# Schematic.net
KiCad netlist of a schematic drawn in Altium Designer
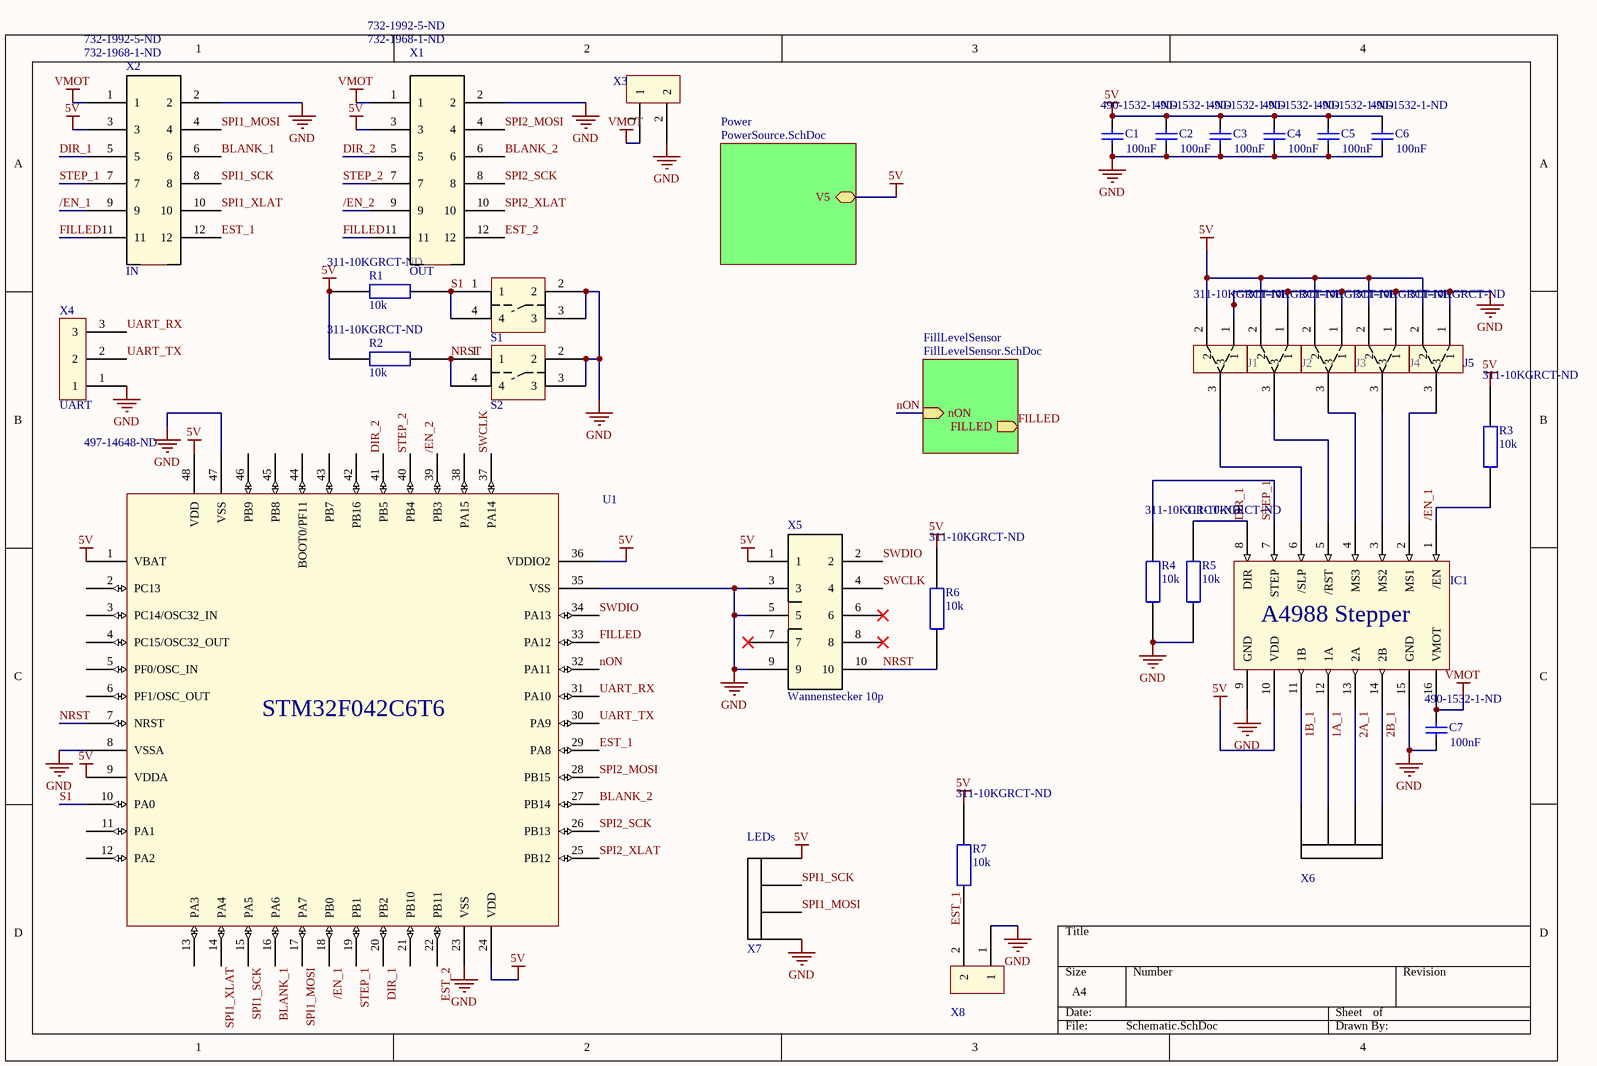
[diagram p0: Schematic.SchDoc]

(export (version "E")
  (design (tool "Eeschema 10.0.6"))
  (components
    (comp (ref "C1")
      (value "100nF")
      (footprint "Res 0603")
      (description "Capacitor")
      (fields
        (field (name "SUPPLIER PART NUMBER 1") "490-1532-1-ND")
        (field (name "Comment") "Cap")
        (field (name "PUBLISHER") "Altium Limited")
      )
      (libsource (lib "Miscellaneous Devices") (part "Cap"))
    )
    (comp (ref "C2")
      (value "100nF")
      (footprint "Res 0603")
      (description "Capacitor")
      (fields
        (field (name "SUPPLIER PART NUMBER 1") "490-1532-1-ND")
        (field (name "Comment") "Cap")
        (field (name "PUBLISHER") "Altium Limited")
      )
      (libsource (lib "Miscellaneous Devices") (part "Cap"))
    )
    (comp (ref "C3")
      (value "100nF")
      (footprint "Res 0603")
      (description "Capacitor")
      (fields
        (field (name "SUPPLIER PART NUMBER 1") "490-1532-1-ND")
        (field (name "Comment") "Cap")
        (field (name "PUBLISHER") "Altium Limited")
      )
      (libsource (lib "Miscellaneous Devices") (part "Cap"))
    )
    (comp (ref "C4")
      (value "100nF")
      (footprint "Res 0603")
      (description "Capacitor")
      (fields
        (field (name "SUPPLIER PART NUMBER 1") "490-1532-1-ND")
        (field (name "Comment") "Cap")
        (field (name "PUBLISHER") "Altium Limited")
      )
      (libsource (lib "Miscellaneous Devices") (part "Cap"))
    )
    (comp (ref "C5")
      (value "100nF")
      (footprint "Res 0603")
      (description "Capacitor")
      (fields
        (field (name "SUPPLIER PART NUMBER 1") "490-1532-1-ND")
        (field (name "Comment") "Cap")
        (field (name "PUBLISHER") "Altium Limited")
      )
      (libsource (lib "Miscellaneous Devices") (part "Cap"))
    )
    (comp (ref "C6")
      (value "100nF")
      (footprint "Res 0603")
      (description "Capacitor")
      (fields
        (field (name "SUPPLIER PART NUMBER 1") "490-1532-1-ND")
        (field (name "Comment") "Cap")
        (field (name "PUBLISHER") "Altium Limited")
      )
      (libsource (lib "Miscellaneous Devices") (part "Cap"))
    )
    (comp (ref "C7")
      (value "100nF")
      (footprint "Res 0603")
      (description "Capacitor")
      (fields
        (field (name "SUPPLIER PART NUMBER 1") "490-1532-1-ND")
        (field (name "Comment") "Cap")
        (field (name "PUBLISHER") "Altium Limited")
      )
      (libsource (lib "Miscellaneous Devices") (part "Cap"))
    )
    (comp (ref "IC1")
      (value "A4988 Stepper")
      (footprint "A4988 Stepper")
      (libsource (lib "Schlib") (part "A4988 Stepper"))
    )
    (comp (ref "J1")
      (value "VCC to GND Jumper")
      (footprint "VCC to GND Jumper")
      (fields (field (name "SUPPLIER PART NUMBER 1") "311-10KGRCT-ND"))
      (libsource (lib "Schlib") (part "VCC to GND Jumper"))
    )
    (comp (ref "J2")
      (value "VCC to GND Jumper")
      (footprint "VCC to GND Jumper")
      (fields (field (name "SUPPLIER PART NUMBER 1") "311-10KGRCT-ND"))
      (libsource (lib "Schlib") (part "VCC to GND Jumper"))
    )
    (comp (ref "J3")
      (value "VCC to GND Jumper")
      (footprint "VCC to GND Jumper")
      (fields (field (name "SUPPLIER PART NUMBER 1") "311-10KGRCT-ND"))
      (libsource (lib "Schlib") (part "VCC to GND Jumper"))
    )
    (comp (ref "J4")
      (value "VCC to GND Jumper")
      (footprint "VCC to GND Jumper")
      (fields (field (name "SUPPLIER PART NUMBER 1") "311-10KGRCT-ND"))
      (libsource (lib "Schlib") (part "VCC to GND Jumper"))
    )
    (comp (ref "J5")
      (value "VCC to GND Jumper")
      (footprint "VCC to GND Jumper")
      (fields (field (name "SUPPLIER PART NUMBER 1") "311-10KGRCT-ND"))
      (libsource (lib "Schlib") (part "VCC to GND Jumper"))
    )
    (comp (ref "R1")
      (value "10k")
      (footprint "Res 0603")
      (fields (field (name "SUPPLIER PART NUMBER 1") "311-10KGRCT-ND"))
      (libsource (lib "Schlib") (part "Res"))
    )
    (comp (ref "R2")
      (value "10k")
      (footprint "Res 0603")
      (fields (field (name "SUPPLIER PART NUMBER 1") "311-10KGRCT-ND"))
      (libsource (lib "Schlib") (part "Res"))
    )
    (comp (ref "R3")
      (value "10k")
      (footprint "Res 0603")
      (fields (field (name "SUPPLIER PART NUMBER 1") "311-10KGRCT-ND"))
      (libsource (lib "Schlib") (part "Res"))
    )
    (comp (ref "R4")
      (value "10k")
      (footprint "Res 0603")
      (fields (field (name "SUPPLIER PART NUMBER 1") "311-10KGRCT-ND"))
      (libsource (lib "Schlib") (part "Res"))
    )
    (comp (ref "R5")
      (value "10k")
      (footprint "Res 0603")
      (fields (field (name "SUPPLIER PART NUMBER 1") "311-10KGRCT-ND"))
      (libsource (lib "Schlib") (part "Res"))
    )
    (comp (ref "R6")
      (value "10k")
      (footprint "Res 0603")
      (fields (field (name "SUPPLIER PART NUMBER 1") "311-10KGRCT-ND"))
      (libsource (lib "Schlib") (part "Res"))
    )
    (comp (ref "R7")
      (value "10k")
      (footprint "Res 0603")
      (fields (field (name "SUPPLIER PART NUMBER 1") "311-10KGRCT-ND"))
      (libsource (lib "Schlib") (part "Res"))
    )
    (comp (ref "S1") (value "Taster") (footprint "Taster") (libsource (lib "Schlib") (part "Taster")))
    (comp (ref "S2") (value "Taster") (footprint "Taster") (libsource (lib "Schlib") (part "Taster")))
    (comp (ref "U1")
      (value "STM32F042C6T6")
      (footprint "LQFP48")
      (fields (field (name "SUPPLIER PART NUMBER 1") "497-14648-ND"))
      (libsource (lib "Schlib") (part "STM32F042C6T6"))
    )
    (comp (ref "X1")
      (value "OUT")
      (footprint "12p Wurth 690 367 28 12 76")
      (fields
        (field (name "SUPPLIER PART NUMBER 1") "732-1968-1-ND")
        (field (name "SUPPLIER PART NUMBER 2") "732-1992-5-ND")
      )
      (libsource (lib "Schlib") (part "12p Connector"))
    )
    (comp (ref "X2")
      (value "IN")
      (footprint "12p Wurth 690 367 28 12 76")
      (fields
        (field (name "SUPPLIER PART NUMBER 1") "732-1968-1-ND")
        (field (name "SUPPLIER PART NUMBER 2") "732-1992-5-ND")
      )
      (libsource (lib "Schlib") (part "12p Connector"))
    )
    (comp (ref "X3")
      (value "2p Connector")
      (footprint "2p 2.54 pitch")
      (libsource (lib "Schlib") (part "2p Connector"))
    )
    (comp (ref "X4")
      (value "UART")
      (footprint "3p 2.54 pitch")
      (libsource (lib "Schlib") (part "3p Connector"))
    )
    (comp (ref "X5")
      (value "Wannenstecker 10p")
      (footprint "Wannenstecker 10p")
      (libsource (lib "Schlib") (part "Wannenstecker 10p"))
    )
    (comp (ref "X6")
      (value "4p Connector")
      (footprint "4p 2.54 pitch Motor Connector")
      (libsource (lib "Schlib") (part "4p Connector"))
    )
    (comp (ref "X7")
      (value "LEDs")
      (footprint "4p 2.54 pitch")
      (libsource (lib "Schlib") (part "4p Connector"))
    )
    (comp (ref "X8")
      (value "2p Connector")
      (footprint "2p 2.54 pitch")
      (libsource (lib "") (part "2p Connector_1"))
    )
  )
  (nets
    (net (code "1") (name "/1A_1") (class "Default")
      (node (ref "IC1") (pin "12") (pinfunction "1A_12") (pintype "output"))
      (node (ref "X6") (pin "3") (pinfunction "3_3") (pintype "passive"))
    )
    (net (code "2") (name "/1B_1") (class "Default")
      (node (ref "IC1") (pin "11") (pinfunction "1B_11") (pintype "output"))
      (node (ref "X6") (pin "4") (pinfunction "4_4") (pintype "passive"))
    )
    (net (code "3") (name "/2A_1") (class "Default")
      (node (ref "IC1") (pin "13") (pinfunction "2A_13") (pintype "output"))
      (node (ref "X6") (pin "2") (pinfunction "2_2") (pintype "passive"))
    )
    (net (code "4") (name "/2B_1") (class "Default")
      (node (ref "IC1") (pin "14") (pinfunction "2B_14") (pintype "output"))
      (node (ref "X6") (pin "1") (pinfunction "1_1") (pintype "passive"))
    )
    (net (code "5") (name "/BLANK_1") (class "Default")
      (node (ref "U1") (pin "16") (pinfunction "PA6_16") (pintype "bidirectional"))
      (node (ref "X2") (pin "6") (pinfunction "6_6") (pintype "passive"))
    )
    (net (code "6") (name "/BLANK_2") (class "Default")
      (node (ref "U1") (pin "27") (pinfunction "PB14_27") (pintype "bidirectional"))
      (node (ref "X1") (pin "6") (pinfunction "6_6") (pintype "passive"))
    )
    (net (code "7") (name "/DIR_1") (class "Default")
      (node (ref "IC1") (pin "8") (pinfunction "DIR_8") (pintype "input"))
      (node (ref "R5") (pin "2") (pinfunction "2_2") (pintype "passive"))
      (node (ref "U1") (pin "20") (pinfunction "PB2_20") (pintype "bidirectional"))
      (node (ref "X2") (pin "5") (pinfunction "5_5") (pintype "passive"))
    )
    (net (code "8") (name "/DIR_2") (class "Default")
      (node (ref "U1") (pin "41") (pinfunction "PB5_41") (pintype "bidirectional"))
      (node (ref "X1") (pin "5") (pinfunction "5_5") (pintype "passive"))
    )
    (net (code "9") (name "/EST_1") (class "Default")
      (node (ref "R7") (pin "1") (pinfunction "1_1") (pintype "passive"))
      (node (ref "U1") (pin "29") (pinfunction "PA8_29") (pintype "bidirectional"))
      (node (ref "X2") (pin "12") (pinfunction "12_12") (pintype "passive"))
      (node (ref "X8") (pin "2") (pinfunction "2_2") (pintype "passive"))
    )
    (net (code "10") (name "/EST_2") (class "Default")
      (node (ref "U1") (pin "22") (pinfunction "PB11_22") (pintype "bidirectional"))
      (node (ref "X1") (pin "12") (pinfunction "12_12") (pintype "passive"))
    )
    (net (code "11") (name "/FILLED") (class "Default")
      (node (ref "U1") (pin "33") (pinfunction "PA12_33") (pintype "bidirectional"))
      (node (ref "X1") (pin "11") (pinfunction "11_11") (pintype "passive"))
      (node (ref "X2") (pin "11") (pinfunction "11_11") (pintype "passive"))
    )
    (net (code "12") (name "/NRST") (class "Default")
      (node (ref "R2") (pin "1") (pinfunction "1_1") (pintype "passive"))
      (node (ref "R6") (pin "1") (pinfunction "1_1") (pintype "passive"))
      (node (ref "S2") (pin "1") (pinfunction "1_1") (pintype "passive"))
      (node (ref "S2") (pin "4") (pinfunction "4_4") (pintype "passive"))
      (node (ref "U1") (pin "7") (pinfunction "NRST_7") (pintype "bidirectional"))
      (node (ref "X5") (pin "10") (pinfunction "10_10") (pintype "passive"))
    )
    (net (code "13") (name "/S1") (class "Default")
      (node (ref "R1") (pin "1") (pinfunction "1_1") (pintype "passive"))
      (node (ref "S1") (pin "1") (pinfunction "1_1") (pintype "passive"))
      (node (ref "S1") (pin "4") (pinfunction "4_4") (pintype "passive"))
      (node (ref "U1") (pin "10") (pinfunction "PA0_10") (pintype "bidirectional"))
    )
    (net (code "14") (name "/SPI1_MOSI") (class "Default")
      (node (ref "U1") (pin "17") (pinfunction "PA7_17") (pintype "bidirectional"))
      (node (ref "X2") (pin "4") (pinfunction "4_4") (pintype "passive"))
      (node (ref "X7") (pin "2") (pinfunction "2_2") (pintype "passive"))
    )
    (net (code "15") (name "/SPI1_SCK") (class "Default")
      (node (ref "U1") (pin "15") (pinfunction "PA5_15") (pintype "bidirectional"))
      (node (ref "X2") (pin "8") (pinfunction "8_8") (pintype "passive"))
      (node (ref "X7") (pin "3") (pinfunction "3_3") (pintype "passive"))
    )
    (net (code "16") (name "/SPI1_XLAT") (class "Default")
      (node (ref "U1") (pin "14") (pinfunction "PA4_14") (pintype "bidirectional"))
      (node (ref "X2") (pin "10") (pinfunction "10_10") (pintype "passive"))
    )
    (net (code "17") (name "/SPI2_MOSI") (class "Default")
      (node (ref "U1") (pin "28") (pinfunction "PB15_28") (pintype "bidirectional"))
      (node (ref "X1") (pin "4") (pinfunction "4_4") (pintype "passive"))
    )
    (net (code "18") (name "/SPI2_SCK") (class "Default")
      (node (ref "U1") (pin "26") (pinfunction "PB13_26") (pintype "bidirectional"))
      (node (ref "X1") (pin "8") (pinfunction "8_8") (pintype "passive"))
    )
    (net (code "19") (name "/SPI2_XLAT") (class "Default")
      (node (ref "U1") (pin "25") (pinfunction "PB12_25") (pintype "bidirectional"))
      (node (ref "X1") (pin "10") (pinfunction "10_10") (pintype "passive"))
    )
    (net (code "20") (name "/STEP_1") (class "Default")
      (node (ref "IC1") (pin "7") (pinfunction "STEP_7") (pintype "input"))
      (node (ref "R4") (pin "2") (pinfunction "2_2") (pintype "passive"))
      (node (ref "U1") (pin "19") (pinfunction "PB1_19") (pintype "bidirectional"))
      (node (ref "X2") (pin "7") (pinfunction "7_7") (pintype "passive"))
    )
    (net (code "21") (name "/STEP_2") (class "Default")
      (node (ref "U1") (pin "40") (pinfunction "PB4_40") (pintype "bidirectional"))
      (node (ref "X1") (pin "7") (pinfunction "7_7") (pintype "passive"))
    )
    (net (code "22") (name "/SWCLK") (class "Default")
      (node (ref "U1") (pin "37") (pinfunction "PA14_37") (pintype "bidirectional"))
      (node (ref "X5") (pin "4") (pinfunction "4_4") (pintype "passive"))
    )
    (net (code "23") (name "/SWDIO") (class "Default")
      (node (ref "U1") (pin "34") (pinfunction "PA13_34") (pintype "bidirectional"))
      (node (ref "X5") (pin "2") (pinfunction "2_2") (pintype "passive"))
    )
    (net (code "24") (name "/UART_RX") (class "Default")
      (node (ref "U1") (pin "31") (pinfunction "PA10_31") (pintype "bidirectional"))
      (node (ref "X4") (pin "3") (pinfunction "3_3") (pintype "passive"))
    )
    (net (code "25") (name "/UART_TX") (class "Default")
      (node (ref "U1") (pin "30") (pinfunction "PA9_30") (pintype "bidirectional"))
      (node (ref "X4") (pin "2") (pinfunction "2_2") (pintype "passive"))
    )
    (net (code "26") (name "/nON") (class "Default")
      (node (ref "U1") (pin "32") (pinfunction "PA11_32") (pintype "bidirectional"))
    )
    (net (code "27") (name "/{slash}EN_1") (class "Default")
      (node (ref "IC1") (pin "1") (pinfunction "/EN_1") (pintype "input"))
      (node (ref "R3") (pin "1") (pinfunction "1_1") (pintype "passive"))
      (node (ref "U1") (pin "18") (pinfunction "PB0_18") (pintype "bidirectional"))
      (node (ref "X2") (pin "9") (pinfunction "9_9") (pintype "passive"))
    )
    (net (code "28") (name "/{slash}EN_2") (class "Default")
      (node (ref "U1") (pin "39") (pinfunction "PB3_39") (pintype "bidirectional"))
      (node (ref "X1") (pin "9") (pinfunction "9_9") (pintype "passive"))
    )
    (net (code "29") (name "5V") (class "Default")
      (node (ref "C1") (pin "2") (pinfunction "2_2") (pintype "passive"))
      (node (ref "C2") (pin "2") (pinfunction "2_2") (pintype "passive"))
      (node (ref "C3") (pin "2") (pinfunction "2_2") (pintype "passive"))
      (node (ref "C4") (pin "2") (pinfunction "2_2") (pintype "passive"))
      (node (ref "C5") (pin "2") (pinfunction "2_2") (pintype "passive"))
      (node (ref "C6") (pin "2") (pinfunction "2_2") (pintype "passive"))
      (node (ref "IC1") (pin "10") (pinfunction "VDD_10") (pintype "power_in"))
      (node (ref "J1") (pin "2") (pinfunction "2_2") (pintype "passive"))
      (node (ref "J2") (pin "2") (pinfunction "2_2") (pintype "passive"))
      (node (ref "J3") (pin "2") (pinfunction "2_2") (pintype "passive"))
      (node (ref "J4") (pin "2") (pinfunction "2_2") (pintype "passive"))
      (node (ref "J5") (pin "2") (pinfunction "2_2") (pintype "passive"))
      (node (ref "R1") (pin "2") (pinfunction "2_2") (pintype "passive"))
      (node (ref "R2") (pin "2") (pinfunction "2_2") (pintype "passive"))
      (node (ref "R3") (pin "2") (pinfunction "2_2") (pintype "passive"))
      (node (ref "R6") (pin "2") (pinfunction "2_2") (pintype "passive"))
      (node (ref "R7") (pin "2") (pinfunction "2_2") (pintype "passive"))
      (node (ref "U1") (pin "1") (pinfunction "VBAT_1") (pintype "power_in"))
      (node (ref "U1") (pin "24") (pinfunction "VDD_24") (pintype "power_in"))
      (node (ref "U1") (pin "36") (pinfunction "VDDIO2_36") (pintype "power_in"))
      (node (ref "U1") (pin "48") (pinfunction "VDD_48") (pintype "power_in"))
      (node (ref "U1") (pin "9") (pinfunction "VDDA_9") (pintype "power_in"))
      (node (ref "X1") (pin "3") (pinfunction "3_3") (pintype "passive"))
      (node (ref "X2") (pin "3") (pinfunction "3_3") (pintype "passive"))
      (node (ref "X5") (pin "1") (pinfunction "1_1") (pintype "passive"))
      (node (ref "X7") (pin "4") (pinfunction "4_4") (pintype "passive"))
    )
    (net (code "30") (name "GND") (class "Default")
      (node (ref "C1") (pin "1") (pinfunction "1_1") (pintype "passive"))
      (node (ref "C2") (pin "1") (pinfunction "1_1") (pintype "passive"))
      (node (ref "C3") (pin "1") (pinfunction "1_1") (pintype "passive"))
      (node (ref "C4") (pin "1") (pinfunction "1_1") (pintype "passive"))
      (node (ref "C5") (pin "1") (pinfunction "1_1") (pintype "passive"))
      (node (ref "C6") (pin "1") (pinfunction "1_1") (pintype "passive"))
      (node (ref "C7") (pin "1") (pinfunction "1_1") (pintype "passive"))
      (node (ref "IC1") (pin "15") (pinfunction "GND_15") (pintype "power_in"))
      (node (ref "IC1") (pin "9") (pinfunction "GND_9") (pintype "power_in"))
      (node (ref "J1") (pin "1") (pinfunction "1_1") (pintype "passive"))
      (node (ref "J2") (pin "1") (pinfunction "1_1") (pintype "passive"))
      (node (ref "J3") (pin "1") (pinfunction "1_1") (pintype "passive"))
      (node (ref "J4") (pin "1") (pinfunction "1_1") (pintype "passive"))
      (node (ref "J5") (pin "1") (pinfunction "1_1") (pintype "passive"))
      (node (ref "R4") (pin "1") (pinfunction "1_1") (pintype "passive"))
      (node (ref "R5") (pin "1") (pinfunction "1_1") (pintype "passive"))
      (node (ref "S1") (pin "2") (pinfunction "2_2") (pintype "passive"))
      (node (ref "S1") (pin "3") (pinfunction "3_3") (pintype "passive"))
      (node (ref "S2") (pin "2") (pinfunction "2_2") (pintype "passive"))
      (node (ref "S2") (pin "3") (pinfunction "3_3") (pintype "passive"))
      (node (ref "U1") (pin "23") (pinfunction "VSS_23") (pintype "power_in"))
      (node (ref "U1") (pin "35") (pinfunction "VSS_35") (pintype "power_in"))
      (node (ref "U1") (pin "47") (pinfunction "VSS_47") (pintype "power_in"))
      (node (ref "U1") (pin "8") (pinfunction "VSSA_8") (pintype "power_in"))
      (node (ref "X1") (pin "2") (pinfunction "2_2") (pintype "passive"))
      (node (ref "X2") (pin "2") (pinfunction "2_2") (pintype "passive"))
      (node (ref "X3") (pin "2") (pinfunction "2_2") (pintype "passive"))
      (node (ref "X4") (pin "1") (pinfunction "1_1") (pintype "passive"))
      (node (ref "X5") (pin "3") (pinfunction "3_3") (pintype "passive"))
      (node (ref "X5") (pin "5") (pinfunction "5_5") (pintype "passive"))
      (node (ref "X5") (pin "9") (pinfunction "9_9") (pintype "passive"))
      (node (ref "X7") (pin "1") (pinfunction "1_1") (pintype "passive"))
      (node (ref "X8") (pin "1") (pinfunction "1_1") (pintype "passive"))
    )
    (net (code "31") (name "Net-(IC1-MS1)") (class "Default")
      (node (ref "IC1") (pin "2") (pinfunction "MS1_2") (pintype "input"))
      (node (ref "J5") (pin "3") (pinfunction "3_3") (pintype "passive"))
    )
    (net (code "32") (name "Net-(IC1-MS2)") (class "Default")
      (node (ref "IC1") (pin "3") (pinfunction "MS2_3") (pintype "input"))
      (node (ref "J4") (pin "3") (pinfunction "3_3") (pintype "passive"))
    )
    (net (code "33") (name "Net-(IC1-MS3)") (class "Default")
      (node (ref "IC1") (pin "4") (pinfunction "MS3_4") (pintype "input"))
      (node (ref "J3") (pin "3") (pinfunction "3_3") (pintype "passive"))
    )
    (net (code "34") (name "Net-(IC1-{slash}RST)") (class "Default")
      (node (ref "IC1") (pin "5") (pinfunction "/RST_5") (pintype "input"))
      (node (ref "J2") (pin "3") (pinfunction "3_3") (pintype "passive"))
    )
    (net (code "35") (name "Net-(IC1-{slash}SLP)") (class "Default")
      (node (ref "IC1") (pin "6") (pinfunction "/SLP_6") (pintype "input"))
      (node (ref "J1") (pin "3") (pinfunction "3_3") (pintype "passive"))
    )
    (net (code "36") (name "VMOT") (class "Default")
      (node (ref "C7") (pin "2") (pinfunction "2_2") (pintype "passive"))
      (node (ref "IC1") (pin "16") (pinfunction "VMOT_16") (pintype "power_in"))
      (node (ref "X1") (pin "1") (pinfunction "1_1") (pintype "passive"))
      (node (ref "X2") (pin "1") (pinfunction "1_1") (pintype "passive"))
      (node (ref "X3") (pin "1") (pinfunction "1_1") (pintype "passive"))
    )
    (net (code "37") (name "unconnected-(U1-BOOT0{slash}PF11-Pad44)") (class "Default")
      (node (ref "U1") (pin "44") (pinfunction "BOOT0/PF11_44") (pintype "bidirectional"))
    )
    (net (code "38") (name "unconnected-(U1-PA1-Pad11)") (class "Default")
      (node (ref "U1") (pin "11") (pinfunction "PA1_11") (pintype "bidirectional"))
    )
    (net (code "39") (name "unconnected-(U1-PA2-Pad12)") (class "Default")
      (node (ref "U1") (pin "12") (pinfunction "PA2_12") (pintype "bidirectional"))
    )
    (net (code "40") (name "unconnected-(U1-PA3-Pad13)") (class "Default")
      (node (ref "U1") (pin "13") (pinfunction "PA3_13") (pintype "bidirectional"))
    )
    (net (code "41") (name "unconnected-(U1-PA15-Pad38)") (class "Default")
      (node (ref "U1") (pin "38") (pinfunction "PA15_38") (pintype "bidirectional"))
    )
    (net (code "42") (name "unconnected-(U1-PB7-Pad43)") (class "Default")
      (node (ref "U1") (pin "43") (pinfunction "PB7_43") (pintype "bidirectional"))
    )
    (net (code "43") (name "unconnected-(U1-PB8-Pad45)") (class "Default")
      (node (ref "U1") (pin "45") (pinfunction "PB8_45") (pintype "bidirectional"))
    )
    (net (code "44") (name "unconnected-(U1-PB9-Pad46)") (class "Default")
      (node (ref "U1") (pin "46") (pinfunction "PB9_46") (pintype "bidirectional"))
    )
    (net (code "45") (name "unconnected-(U1-PB10-Pad21)") (class "Default")
      (node (ref "U1") (pin "21") (pinfunction "PB10_21") (pintype "bidirectional"))
    )
    (net (code "46") (name "unconnected-(U1-PB16-Pad42)") (class "Default")
      (node (ref "U1") (pin "42") (pinfunction "PB16_42") (pintype "bidirectional"))
    )
    (net (code "47") (name "unconnected-(U1-PC13-Pad2)") (class "Default")
      (node (ref "U1") (pin "2") (pinfunction "PC13_2") (pintype "bidirectional"))
    )
    (net (code "48") (name "unconnected-(U1-PC14{slash}OSC32_IN-Pad3)") (class "Default")
      (node (ref "U1") (pin "3") (pinfunction "PC14/OSC32_IN_3") (pintype "bidirectional"))
    )
    (net (code "49") (name "unconnected-(U1-PC15{slash}OSC32_OUT-Pad4)") (class "Default")
      (node (ref "U1") (pin "4") (pinfunction "PC15/OSC32_OUT_4") (pintype "bidirectional"))
    )
    (net (code "50") (name "unconnected-(U1-PF0{slash}OSC_IN-Pad5)") (class "Default")
      (node (ref "U1") (pin "5") (pinfunction "PF0/OSC_IN_5") (pintype "bidirectional"))
    )
    (net (code "51") (name "unconnected-(U1-PF1{slash}OSC_OUT-Pad6)") (class "Default")
      (node (ref "U1") (pin "6") (pinfunction "PF1/OSC_OUT_6") (pintype "bidirectional"))
    )
    (net (code "52") (name "unconnected-(X5-Pad6)") (class "Default")
      (node (ref "X5") (pin "6") (pinfunction "6_6") (pintype "passive+no_connect"))
    )
    (net (code "53") (name "unconnected-(X5-Pad7)") (class "Default")
      (node (ref "X5") (pin "7") (pinfunction "7_7") (pintype "passive+no_connect"))
    )
    (net (code "54") (name "unconnected-(X5-Pad8)") (class "Default")
      (node (ref "X5") (pin "8") (pinfunction "8_8") (pintype "passive+no_connect"))
    )
  )
)
